# main.net
KiCad netlist of a schematic drawn in Altium Designer
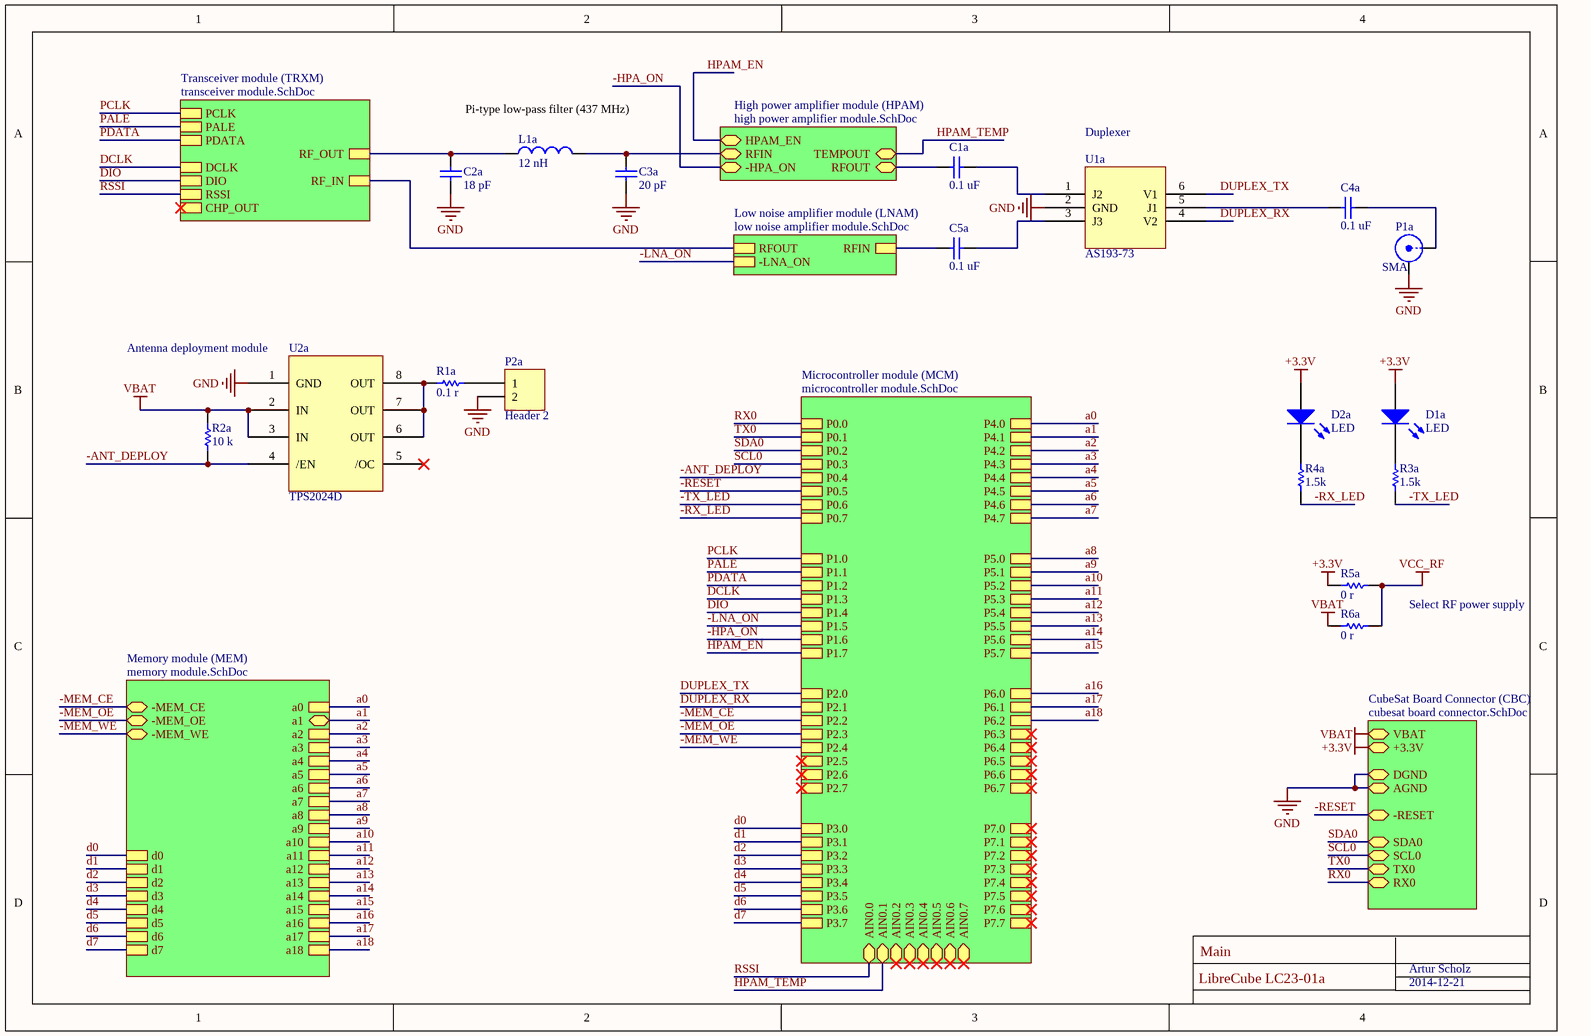
[diagram p0: main.SchDoc]

(export (version "E")
  (design (tool "Eeschema 10.0.6"))
  (components
    (comp (ref "C1a")
      (value "0.1 uF")
      (footprint "0603")
      (description "Capacitor")
      (libsource (lib "allspace_schem") (part "Capacitor"))
    )
    (comp (ref "C2a")
      (value "18 pF")
      (footprint "0603")
      (description "Capacitor")
      (libsource (lib "allspace_schem") (part "Capacitor"))
    )
    (comp (ref "C3a")
      (value "20 pF")
      (footprint "0603")
      (description "Capacitor")
      (libsource (lib "allspace_schem") (part "Capacitor"))
    )
    (comp (ref "C4a")
      (value "0.1 uF")
      (footprint "0603")
      (description "Capacitor")
      (libsource (lib "allspace_schem") (part "Capacitor"))
    )
    (comp (ref "C5a")
      (value "0.1 uF")
      (footprint "0603")
      (description "Capacitor")
      (libsource (lib "allspace_schem") (part "Capacitor"))
    )
    (comp (ref "D1a")
      (value "LED")
      (footprint "0603")
      (description "Typical INFRARED GaAs LED")
      (libsource (lib "allspace_schem") (part "LED"))
    )
    (comp (ref "D2a")
      (value "LED")
      (footprint "0603")
      (description "Typical INFRARED GaAs LED")
      (libsource (lib "allspace_schem") (part "LED"))
    )
    (comp (ref "L1a")
      (value "12 nH")
      (footprint "0603")
      (description "Inductor")
      (libsource (lib "allspace_schem") (part "Inductor"))
    )
    (comp (ref "P1a")
      (value "SMA")
      (footprint "SMA")
      (description "SMA Connector")
      (fields (field (name "PUBLISHER") "Altium Limited"))
      (libsource (lib "allspace_schem") (part "SMA"))
    )
    (comp (ref "P2a")
      (value "Header 2")
      (footprint "HDR1X2")
      (description "Header, 2-Pin")
      (fields (field (name "PUBLISHER") "Altium Limited"))
      (libsource (lib "allspace_schem") (part "Header 2"))
    )
    (comp (ref "R1a")
      (value "0.1 r")
      (footprint "2512")
      (description "Resistor")
      (libsource (lib "allspace_schem") (part "Resistor"))
    )
    (comp (ref "R2a")
      (value "10 k")
      (footprint "0603")
      (fields (field (name "PUBLISHER") "Altium Limited"))
      (libsource (lib "Miscellaneous Devices") (part "Res1"))
    )
    (comp (ref "R3a")
      (value "1.5k")
      (footprint "0603")
      (description "Resistor")
      (libsource (lib "allspace_schem") (part "Resistor"))
    )
    (comp (ref "R4a")
      (value "1.5k")
      (footprint "0603")
      (description "Resistor")
      (libsource (lib "allspace_schem") (part "Resistor"))
    )
    (comp (ref "R5a")
      (value "0 r")
      (footprint "0603")
      (description "Resistor")
      (libsource (lib "allspace_schem") (part "Resistor"))
    )
    (comp (ref "R6a")
      (value "0 r")
      (footprint "0603")
      (description "Resistor")
      (libsource (lib "allspace_schem") (part "Resistor"))
    )
    (comp (ref "U1a")
      (value "AS193-73")
      (footprint "SOT-6")
      (description "RF SPDT Switch")
      (libsource (lib "allspace_schem") (part "AS193-73"))
    )
    (comp (ref "U2a")
      (value "TPS2024D")
      (footprint "SO-8")
      (description "296-2564-5-ND")
      (libsource (lib "allspace_schem") (part "TPS2024"))
    )
  )
  (nets
    (net (code "1") (name "+3.3V") (class "Default")
      (node (ref "D1a") (pin "1") (pinfunction "A_1") (pintype "passive"))
      (node (ref "D2a") (pin "1") (pinfunction "A_1") (pintype "passive"))
      (node (ref "R5a") (pin "2") (pinfunction "2_2") (pintype "passive"))
    )
    (net (code "2") (name "/-ANT_DEPLOY") (class "Default")
      (node (ref "R2a") (pin "1") (pinfunction "1_1") (pintype "passive"))
      (node (ref "U2a") (pin "4") (pinfunction "/EN_4") (pintype "passive"))
    )
    (net (code "9") (name "/-RX_LED") (class "Default")
      (node (ref "R4a") (pin "2") (pinfunction "2_2") (pintype "passive"))
    )
    (net (code "10") (name "/-TX_LED") (class "Default")
      (node (ref "R3a") (pin "2") (pinfunction "2_2") (pintype "passive"))
    )
    (net (code "20") (name "/DUPLEX_RX") (class "Default")
      (node (ref "U1a") (pin "4") (pinfunction "V2_4") (pintype "passive"))
    )
    (net (code "21") (name "/DUPLEX_TX") (class "Default")
      (node (ref "U1a") (pin "6") (pinfunction "V1_6") (pintype "passive"))
    )
    (net (code "43") (name "/RFIN") (class "Default")
      (node (ref "C5a") (pin "1") (pinfunction "1_1") (pintype "passive"))
    )
    (net (code "44") (name "/RFIN_1") (class "Default")
      (node (ref "C3a") (pin "2") (pinfunction "2_2") (pintype "passive"))
      (node (ref "L1a") (pin "2") (pinfunction "2_2") (pintype "passive"))
    )
    (net (code "45") (name "/RFOUT") (class "Default")
      (node (ref "C1a") (pin "1") (pinfunction "1_1") (pintype "passive"))
    )
    (net (code "47") (name "/RF_OUT") (class "Default")
      (node (ref "C2a") (pin "2") (pinfunction "2_2") (pintype "passive"))
      (node (ref "L1a") (pin "1") (pinfunction "1_1") (pintype "passive"))
    )
    (net (code "80") (name "GND") (class "Default")
      (node (ref "C2a") (pin "1") (pinfunction "1_1") (pintype "passive"))
      (node (ref "C3a") (pin "1") (pinfunction "1_1") (pintype "passive"))
      (node (ref "P1a") (pin "2") (pinfunction "Y_2") (pintype "passive"))
      (node (ref "P2a") (pin "2") (pinfunction "2_2") (pintype "passive"))
      (node (ref "U1a") (pin "2") (pinfunction "GND_2") (pintype "passive"))
      (node (ref "U2a") (pin "1") (pinfunction "GND_1") (pintype "passive"))
    )
    (net (code "81") (name "Net-(D1a-K)") (class "Default")
      (node (ref "D1a") (pin "2") (pinfunction "K_2") (pintype "passive"))
      (node (ref "R3a") (pin "1") (pinfunction "1_1") (pintype "passive"))
    )
    (net (code "82") (name "Net-(D2a-K)") (class "Default")
      (node (ref "D2a") (pin "2") (pinfunction "K_2") (pintype "passive"))
      (node (ref "R4a") (pin "1") (pinfunction "1_1") (pintype "passive"))
    )
    (net (code "83") (name "Net-(P1a-X)") (class "Default")
      (node (ref "C4a") (pin "1") (pinfunction "1_1") (pintype "passive"))
      (node (ref "P1a") (pin "1") (pinfunction "X_1") (pintype "passive"))
    )
    (net (code "84") (name "Net-(P2a-Pad1)") (class "Default")
      (node (ref "P2a") (pin "1") (pinfunction "1_1") (pintype "passive"))
      (node (ref "R1a") (pin "2") (pinfunction "2_2") (pintype "passive"))
    )
    (net (code "85") (name "Net-(R1a-Pad1)") (class "Default")
      (node (ref "R1a") (pin "1") (pinfunction "1_1") (pintype "passive"))
      (node (ref "U2a") (pin "6") (pinfunction "OUT_6") (pintype "passive"))
      (node (ref "U2a") (pin "7") (pinfunction "OUT_7") (pintype "passive"))
      (node (ref "U2a") (pin "8") (pinfunction "OUT_8") (pintype "passive"))
    )
    (net (code "86") (name "Net-(U1a-J1)") (class "Default")
      (node (ref "C4a") (pin "2") (pinfunction "2_2") (pintype "passive"))
      (node (ref "U1a") (pin "5") (pinfunction "J1_5") (pintype "passive"))
    )
    (net (code "87") (name "Net-(U1a-J2)") (class "Default")
      (node (ref "C1a") (pin "2") (pinfunction "2_2") (pintype "passive"))
      (node (ref "U1a") (pin "1") (pinfunction "J2_1") (pintype "passive"))
    )
    (net (code "88") (name "Net-(U1a-J3)") (class "Default")
      (node (ref "C5a") (pin "2") (pinfunction "2_2") (pintype "passive"))
      (node (ref "U1a") (pin "3") (pinfunction "J3_3") (pintype "passive"))
    )
    (net (code "89") (name "VBAT") (class "Default")
      (node (ref "R2a") (pin "2") (pinfunction "2_2") (pintype "passive"))
      (node (ref "R6a") (pin "2") (pinfunction "2_2") (pintype "passive"))
      (node (ref "U2a") (pin "2") (pinfunction "IN_2") (pintype "passive"))
      (node (ref "U2a") (pin "3") (pinfunction "IN_3") (pintype "passive"))
    )
    (net (code "90") (name "VCC_RF") (class "Default")
      (node (ref "R5a") (pin "1") (pinfunction "1_1") (pintype "passive"))
      (node (ref "R6a") (pin "1") (pinfunction "1_1") (pintype "passive"))
    )
    (net (code "91") (name "unconnected-(U2a-{slash}OC-Pad5)") (class "Default")
      (node (ref "U2a") (pin "5") (pinfunction "/OC_5") (pintype "passive+no_connect"))
    )
  )
)
